# Sensor_Motor.net
KiCad netlist of a schematic drawn in Altium Designer
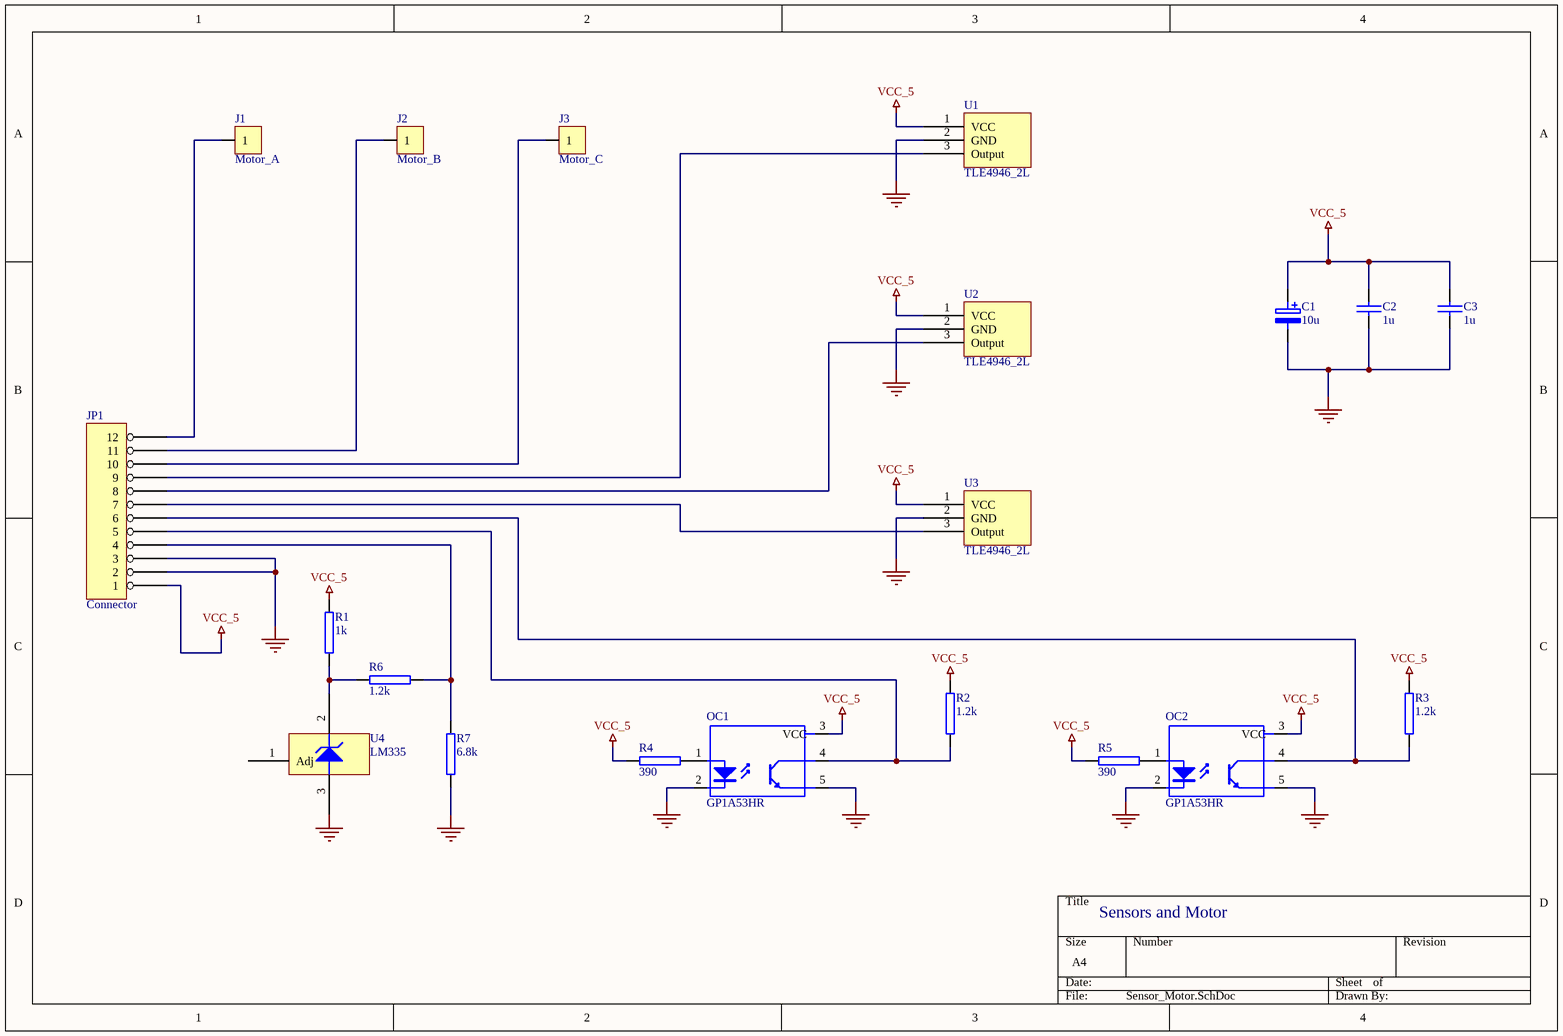
[diagram p0: Sensor_Motor.SchDoc]

(export (version "E")
  (design (tool "Eeschema 10.0.6"))
  (components
    (comp (ref "C1") (value "10u") (footprint "M_CAPSM1") (libsource (lib "Sch_Lib_24") (part "CAP_ELECTRO")))
    (comp (ref "C2") (value "1u") (footprint "M_1206") (libsource (lib "Sch_Lib_24") (part "CAP")))
    (comp (ref "C3") (value "1u") (footprint "M_1206") (libsource (lib "Sch_Lib_24") (part "CAP")))
    (comp (ref "J1")
      (value "Motor_A")
      (footprint "M_SINGLE_SMD")
      (libsource (lib "Sch_Lib_24") (part "CON1"))
    )
    (comp (ref "J2")
      (value "Motor_B")
      (footprint "M_SINGLE_SMD")
      (libsource (lib "Sch_Lib_24") (part "CON1"))
    )
    (comp (ref "J3")
      (value "Motor_C")
      (footprint "M_SINGLE_SMD")
      (libsource (lib "Sch_Lib_24") (part "CON1"))
    )
    (comp (ref "JP1")
      (value "Connector")
      (footprint "m_sip12")
      (libsource (lib "Sch_Lib_24") (part "HEADER 12"))
    )
    (comp (ref "OC1")
      (value "GP1A53HR")
      (footprint "M_PHOTO3")
      (libsource (lib "Sch_Lib_24") (part "PHOTO_INTR"))
    )
    (comp (ref "OC2")
      (value "GP1A53HR")
      (footprint "M_PHOTO3")
      (libsource (lib "Sch_Lib_24") (part "PHOTO_INTR"))
    )
    (comp (ref "R1") (value "1k") (footprint "M_1206") (libsource (lib "Sch_Lib_24") (part "RES2")))
    (comp (ref "R2") (value "1.2k") (footprint "M_1206") (libsource (lib "Sch_Lib_24") (part "RES2")))
    (comp (ref "R3") (value "1.2k") (footprint "M_1206") (libsource (lib "Sch_Lib_24") (part "RES2")))
    (comp (ref "R4") (value "390") (footprint "M_1206") (libsource (lib "Sch_Lib_24") (part "RES2")))
    (comp (ref "R5") (value "390") (footprint "M_1206") (libsource (lib "Sch_Lib_24") (part "RES2")))
    (comp (ref "R6") (value "1.2k") (footprint "M_1206") (libsource (lib "Sch_Lib_24") (part "RES2")))
    (comp (ref "R7") (value "6.8k") (footprint "M_1206") (libsource (lib "Sch_Lib_24") (part "RES2")))
    (comp (ref "U1")
      (value "TLE4946_2L")
      (footprint "M_HALL2")
      (libsource (lib "Sch_Lib_24") (part "UGN_3503"))
    )
    (comp (ref "U2")
      (value "TLE4946_2L")
      (footprint "M_HALL2")
      (libsource (lib "Sch_Lib_24") (part "UGN_3503"))
    )
    (comp (ref "U3")
      (value "TLE4946_2L")
      (footprint "M_HALL2")
      (libsource (lib "Sch_Lib_24") (part "UGN_3503"))
    )
    (comp (ref "U4") (value "LM335") (footprint "M_TSENSE1") (libsource (lib "Sch_Lib_24") (part "LM_335")))
  )
  (nets
    (net (code "1") (name "GND") (class "Default")
      (node (ref "C1") (pin "2") (pintype "passive"))
      (node (ref "C2") (pin "2") (pintype "passive"))
      (node (ref "C3") (pin "2") (pintype "passive"))
      (node (ref "JP1") (pin "2") (pinfunction "2_2") (pintype "passive"))
      (node (ref "JP1") (pin "3") (pinfunction "3_3") (pintype "passive"))
      (node (ref "OC1") (pin "2") (pintype "passive"))
      (node (ref "OC1") (pin "5") (pintype "passive"))
      (node (ref "OC2") (pin "2") (pintype "passive"))
      (node (ref "OC2") (pin "5") (pintype "passive"))
      (node (ref "R7") (pin "1") (pintype "passive"))
      (node (ref "U1") (pin "2") (pinfunction "GND_2") (pintype "passive"))
      (node (ref "U2") (pin "2") (pinfunction "GND_2") (pintype "passive"))
      (node (ref "U3") (pin "2") (pinfunction "GND_2") (pintype "passive"))
      (node (ref "U4") (pin "3") (pinfunction "A_3") (pintype "passive"))
    )
    (net (code "2") (name "Net-(J1-Pad1)") (class "Default")
      (node (ref "J1") (pin "1") (pinfunction "1_1") (pintype "passive"))
      (node (ref "JP1") (pin "12") (pinfunction "12_12") (pintype "passive"))
    )
    (net (code "3") (name "Net-(J2-Pad1)") (class "Default")
      (node (ref "J2") (pin "1") (pinfunction "1_1") (pintype "passive"))
      (node (ref "JP1") (pin "11") (pinfunction "11_11") (pintype "passive"))
    )
    (net (code "4") (name "Net-(J3-Pad1)") (class "Default")
      (node (ref "J3") (pin "1") (pinfunction "1_1") (pintype "passive"))
      (node (ref "JP1") (pin "10") (pinfunction "10_10") (pintype "passive"))
    )
    (net (code "5") (name "Net-(JP1-Pad4)") (class "Default")
      (node (ref "JP1") (pin "4") (pinfunction "4_4") (pintype "passive"))
      (node (ref "R6") (pin "1") (pintype "passive"))
      (node (ref "R7") (pin "2") (pintype "passive"))
    )
    (net (code "6") (name "Net-(JP1-Pad5)") (class "Default")
      (node (ref "JP1") (pin "5") (pinfunction "5_5") (pintype "passive"))
      (node (ref "OC1") (pin "4") (pintype "passive"))
      (node (ref "R2") (pin "1") (pintype "passive"))
    )
    (net (code "7") (name "Net-(JP1-Pad6)") (class "Default")
      (node (ref "JP1") (pin "6") (pinfunction "6_6") (pintype "passive"))
      (node (ref "OC2") (pin "4") (pintype "passive"))
      (node (ref "R3") (pin "1") (pintype "passive"))
    )
    (net (code "8") (name "Net-(OC1-Pad1)") (class "Default")
      (node (ref "OC1") (pin "1") (pintype "passive"))
      (node (ref "R4") (pin "2") (pintype "passive"))
    )
    (net (code "9") (name "Net-(OC2-Pad1)") (class "Default")
      (node (ref "OC2") (pin "1") (pintype "passive"))
      (node (ref "R5") (pin "2") (pintype "passive"))
    )
    (net (code "10") (name "Net-(U1-Output)") (class "Default")
      (node (ref "JP1") (pin "9") (pinfunction "9_9") (pintype "passive"))
      (node (ref "U1") (pin "3") (pinfunction "Output_3") (pintype "passive"))
    )
    (net (code "11") (name "Net-(U2-Output)") (class "Default")
      (node (ref "JP1") (pin "8") (pinfunction "8_8") (pintype "passive"))
      (node (ref "U2") (pin "3") (pinfunction "Output_3") (pintype "passive"))
    )
    (net (code "12") (name "Net-(U3-Output)") (class "Default")
      (node (ref "JP1") (pin "7") (pinfunction "7_7") (pintype "passive"))
      (node (ref "U3") (pin "3") (pinfunction "Output_3") (pintype "passive"))
    )
    (net (code "13") (name "Net-(U4-K)") (class "Default")
      (node (ref "R1") (pin "1") (pintype "passive"))
      (node (ref "R6") (pin "2") (pintype "passive"))
      (node (ref "U4") (pin "2") (pinfunction "K_2") (pintype "passive"))
    )
    (net (code "14") (name "VCC_5") (class "Default")
      (node (ref "C1") (pin "1") (pintype "passive"))
      (node (ref "C2") (pin "1") (pintype "passive"))
      (node (ref "C3") (pin "1") (pintype "passive"))
      (node (ref "JP1") (pin "1") (pinfunction "1_1") (pintype "passive"))
      (node (ref "OC1") (pin "3") (pinfunction "VCC_3") (pintype "passive"))
      (node (ref "OC2") (pin "3") (pinfunction "VCC_3") (pintype "passive"))
      (node (ref "R1") (pin "2") (pintype "passive"))
      (node (ref "R2") (pin "2") (pintype "passive"))
      (node (ref "R3") (pin "2") (pintype "passive"))
      (node (ref "R4") (pin "1") (pintype "passive"))
      (node (ref "R5") (pin "1") (pintype "passive"))
      (node (ref "U1") (pin "1") (pinfunction "VCC_1") (pintype "passive"))
      (node (ref "U2") (pin "1") (pinfunction "VCC_1") (pintype "passive"))
      (node (ref "U3") (pin "1") (pinfunction "VCC_1") (pintype "passive"))
    )
    (net (code "15") (name "unconnected-(U4-Adj-Pad1)") (class "Default")
      (node (ref "U4") (pin "1") (pinfunction "Adj_1") (pintype "passive"))
    )
  )
)
